# Active_Load.net
KiCad netlist of a schematic drawn in EAGLE
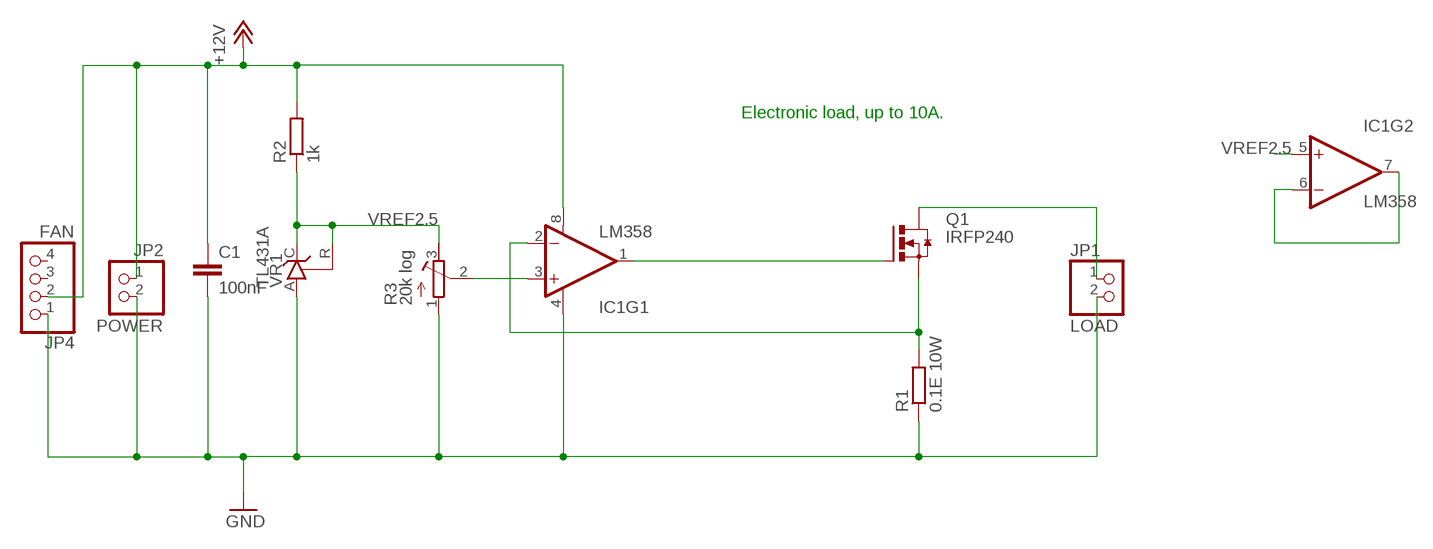
[diagram p0: schematic, sheet 1]

(export (version "E")
  (design (tool "Eeschema 10.0.6"))
  (components
    (comp (ref "C1")
      (value "100nF")
      (footprint "eagle-import:C025-040X050")
      (libsource (lib "eagle-import") (part "C-EU025-040X050"))
    )
    (comp (ref "IC1")
      (value "LM358")
      (footprint "eagle-import:DIP08")
      (libsource (lib "eagle-import") (part "LM358"))
    )
    (comp (ref "JP1")
      (value "LOAD")
      (footprint "eagle-import:1X02")
      (libsource (lib "eagle-import") (part "PINHD-1X2"))
    )
    (comp (ref "JP2")
      (value "POWER")
      (footprint "eagle-import:1X02")
      (libsource (lib "eagle-import") (part "PINHD-1X2"))
    )
    (comp (ref "JP4")
      (value "FAN")
      (footprint "eagle-import:1X04")
      (libsource (lib "eagle-import") (part "PINHD-1X4"))
    )
    (comp (ref "Q1")
      (value "IRFP240")
      (footprint "eagle-import:TO247BV")
      (libsource (lib "eagle-import") (part "IRFP240"))
    )
    (comp (ref "R1")
      (value "0.1E 10W")
      (footprint "eagle-import:0922_22")
      (libsource (lib "eagle-import") (part "R-EU_0922/22"))
    )
    (comp (ref "R2")
      (value "1k")
      (footprint "eagle-import:0411_12")
      (libsource (lib "eagle-import") (part "R-EU_0411/12"))
    )
    (comp (ref "R3")
      (value "20k log")
      (footprint "eagle-import:RTRIM74W")
      (libsource (lib "eagle-import") (part "R-TRIMM74W"))
    )
    (comp (ref "VR1")
      (value "TL431A")
      (footprint "eagle-import:TO92-CLP")
      (libsource (lib "eagle-import") (part "TL431CLP"))
    )
  )
  (nets
    (net (code "1") (name "+12V") (class "Default")
      (node (ref "C1") (pin "1") (pinfunction "1_1") (pintype "passive"))
      (node (ref "IC1") (pin "8") (pinfunction "V+_8") (pintype "power_in"))
      (node (ref "JP2") (pin "1") (pinfunction "1_1") (pintype "passive"))
      (node (ref "JP4") (pin "2") (pinfunction "2_2") (pintype "passive"))
      (node (ref "R2") (pin "2") (pinfunction "2_2") (pintype "passive"))
    )
    (net (code "2") (name "/VREF2.5") (class "Default")
      (node (ref "IC1") (pin "5") (pinfunction "+IN_5") (pintype "input"))
      (node (ref "R2") (pin "1") (pinfunction "1_1") (pintype "passive"))
      (node (ref "R3") (pin "3") (pinfunction "E_3") (pintype "passive"))
      (node (ref "VR1") (pin "C") (pinfunction "C_C") (pintype "passive"))
      (node (ref "VR1") (pin "R") (pinfunction "R_R") (pintype "passive"))
    )
    (net (code "3") (name "GND") (class "Default")
      (node (ref "C1") (pin "2") (pinfunction "2_2") (pintype "passive"))
      (node (ref "IC1") (pin "4") (pinfunction "V-_4") (pintype "power_in"))
      (node (ref "JP1") (pin "2") (pinfunction "2_2") (pintype "passive"))
      (node (ref "JP2") (pin "2") (pinfunction "2_2") (pintype "passive"))
      (node (ref "JP4") (pin "1") (pinfunction "1_1") (pintype "passive"))
      (node (ref "R1") (pin "1") (pinfunction "1_1") (pintype "passive"))
      (node (ref "R3") (pin "1") (pinfunction "A_1") (pintype "passive"))
      (node (ref "VR1") (pin "A") (pinfunction "A_A") (pintype "passive"))
    )
    (net (code "4") (name "Net-(IC1A-+IN)") (class "Default")
      (node (ref "IC1") (pin "3") (pinfunction "+IN_3") (pintype "input"))
      (node (ref "R3") (pin "2") (pinfunction "S_2") (pintype "passive"))
    )
    (net (code "5") (name "Net-(IC1A--IN)") (class "Default")
      (node (ref "IC1") (pin "2") (pinfunction "-IN_2") (pintype "input"))
      (node (ref "Q1") (pin "S") (pinfunction "S_S") (pintype "passive"))
      (node (ref "R1") (pin "2") (pinfunction "2_2") (pintype "passive"))
    )
    (net (code "6") (name "Net-(IC1A-OUT)") (class "Default")
      (node (ref "IC1") (pin "1") (pinfunction "OUT_1") (pintype "output"))
      (node (ref "Q1") (pin "G") (pinfunction "G_G") (pintype "passive"))
    )
    (net (code "7") (name "Net-(IC1B--IN)") (class "Default")
      (node (ref "IC1") (pin "6") (pinfunction "-IN_6") (pintype "input"))
      (node (ref "IC1") (pin "7") (pinfunction "OUT_7") (pintype "output"))
    )
    (net (code "8") (name "Net-(JP1-Pad1)") (class "Default")
      (node (ref "JP1") (pin "1") (pinfunction "1_1") (pintype "passive"))
      (node (ref "Q1") (pin "D") (pinfunction "D_D") (pintype "passive"))
    )
    (net (code "9") (name "unconnected-(JP4-Pad3)") (class "Default")
      (node (ref "JP4") (pin "3") (pinfunction "3_3") (pintype "passive"))
    )
    (net (code "10") (name "unconnected-(JP4-Pad4)") (class "Default")
      (node (ref "JP4") (pin "4") (pinfunction "4_4") (pintype "passive"))
    )
  )
)
